# main.net
KiCad netlist of a schematic drawn in Altium Designer
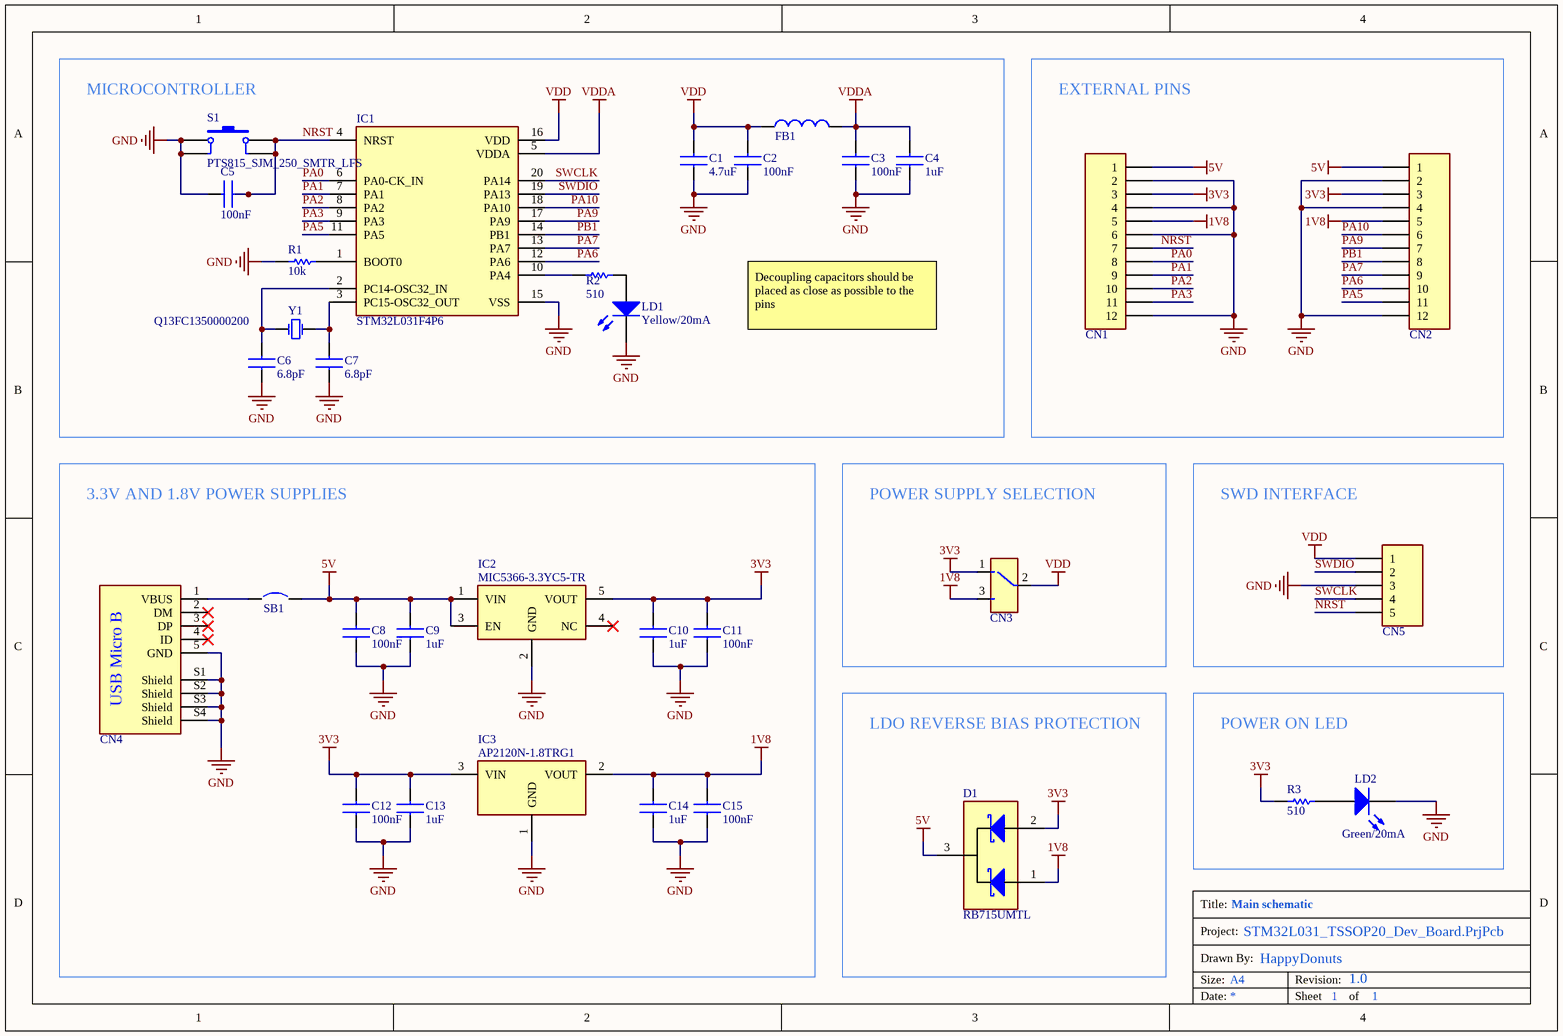
[diagram p0: main.SchDoc]

(export (version "E")
  (design (tool "Eeschema 10.0.6"))
  (components
    (comp (ref "C1")
      (value "4.7uF")
      (footprint "STM32L031_TSSOP20_Dev_Board:CAPC2012X135N")
      (description "Capacitor")
      (fields
        (field (name "MANUFACTURER_PART_NUMBER") "CL21A475KBQNNNE")
        (field (name "MOUSER PART NUMBER") "187-CL21A475KBQNNNE")
      )
      (libsource (lib "STM32L031_TSSOP20_Dev_Board") (part "CL21A475KBQNNNE"))
    )
    (comp (ref "C2")
      (value "100nF")
      (footprint "STM32L031_TSSOP20_Dev_Board:CAPC2012X94N")
      (description "Capacitor")
      (fields
        (field (name "MANUFACTURER_PART_NUMBER") "CL21B104KBCNNNC")
        (field (name "MOUSER PART NUMBER") "187-CL21B104KBCNNNC")
      )
      (libsource (lib "STM32L031_TSSOP20_Dev_Board") (part "CL21B104KBCNNNC"))
    )
    (comp (ref "C3")
      (value "100nF")
      (footprint "STM32L031_TSSOP20_Dev_Board:CAPC2012X94N")
      (description "Capacitor")
      (fields
        (field (name "MANUFACTURER_PART_NUMBER") "CL21B104KBCNNNC")
        (field (name "MOUSER PART NUMBER") "187-CL21B104KBCNNNC")
      )
      (libsource (lib "STM32L031_TSSOP20_Dev_Board") (part "CL21B104KBCNNNC"))
    )
    (comp (ref "C4")
      (value "1uF")
      (footprint "STM32L031_TSSOP20_Dev_Board:CAPC2012X135N")
      (description "Capacitor")
      (fields
        (field (name "MANUFACTURER_PART_NUMBER") "CL21B105KBFNNNE")
        (field (name "MOUSER PART NUMBER") "187-CL21B105KBFNNNE")
      )
      (libsource (lib "STM32L031_TSSOP20_Dev_Board") (part "CL21B105KBFNNNE"))
    )
    (comp (ref "C5")
      (value "100nF")
      (footprint "STM32L031_TSSOP20_Dev_Board:CAPC2012X94N")
      (description "Capacitor")
      (fields
        (field (name "MANUFACTURER_PART_NUMBER") "CL21B104KBCNNNC")
        (field (name "MOUSER PART NUMBER") "187-CL21B104KBCNNNC")
      )
      (libsource (lib "STM32L031_TSSOP20_Dev_Board") (part "CL21B104KBCNNNC"))
    )
    (comp (ref "C6")
      (value "6.8pF")
      (footprint "STM32L031_TSSOP20_Dev_Board:CAPC2012X94N")
      (description "Capacitor")
      (fields
        (field (name "MANUFACTURER_PART_NUMBER") "CC0805CRNPO9BN6R8")
        (field (name "MOUSER PART NUMBER") "603-CC805CRNPO9BN6R8")
      )
      (libsource (lib "STM32L031_TSSOP20_Dev_Board") (part "CC0805CRNPO9BN6R8"))
    )
    (comp (ref "C7")
      (value "6.8pF")
      (footprint "STM32L031_TSSOP20_Dev_Board:CAPC2012X94N")
      (description "Capacitor")
      (fields
        (field (name "MANUFACTURER_PART_NUMBER") "CC0805CRNPO9BN6R8")
        (field (name "MOUSER PART NUMBER") "603-CC805CRNPO9BN6R8")
      )
      (libsource (lib "STM32L031_TSSOP20_Dev_Board") (part "CC0805CRNPO9BN6R8"))
    )
    (comp (ref "C8")
      (value "100nF")
      (footprint "STM32L031_TSSOP20_Dev_Board:CAPC2012X94N")
      (description "Capacitor")
      (fields
        (field (name "MANUFACTURER_PART_NUMBER") "CL21B104KBCNNNC")
        (field (name "MOUSER PART NUMBER") "187-CL21B104KBCNNNC")
      )
      (libsource (lib "STM32L031_TSSOP20_Dev_Board") (part "CL21B104KBCNNNC"))
    )
    (comp (ref "C9")
      (value "1uF")
      (footprint "STM32L031_TSSOP20_Dev_Board:CAPC2012X135N")
      (description "Capacitor")
      (fields
        (field (name "MANUFACTURER_PART_NUMBER") "CL21B105KBFNNNE")
        (field (name "MOUSER PART NUMBER") "187-CL21B105KBFNNNE")
      )
      (libsource (lib "STM32L031_TSSOP20_Dev_Board") (part "CL21B105KBFNNNE"))
    )
    (comp (ref "C10")
      (value "1uF")
      (footprint "STM32L031_TSSOP20_Dev_Board:CAPC2012X135N")
      (description "Capacitor")
      (fields
        (field (name "MANUFACTURER_PART_NUMBER") "CL21B105KBFNNNE")
        (field (name "MOUSER PART NUMBER") "187-CL21B105KBFNNNE")
      )
      (libsource (lib "STM32L031_TSSOP20_Dev_Board") (part "CL21B105KBFNNNE"))
    )
    (comp (ref "C11")
      (value "100nF")
      (footprint "STM32L031_TSSOP20_Dev_Board:CAPC2012X94N")
      (description "Capacitor")
      (fields
        (field (name "MANUFACTURER_PART_NUMBER") "CL21B104KBCNNNC")
        (field (name "MOUSER PART NUMBER") "187-CL21B104KBCNNNC")
      )
      (libsource (lib "STM32L031_TSSOP20_Dev_Board") (part "CL21B104KBCNNNC"))
    )
    (comp (ref "C12")
      (value "100nF")
      (footprint "STM32L031_TSSOP20_Dev_Board:CAPC2012X94N")
      (description "Capacitor")
      (fields
        (field (name "MANUFACTURER_PART_NUMBER") "CL21B104KBCNNNC")
        (field (name "MOUSER PART NUMBER") "187-CL21B104KBCNNNC")
      )
      (libsource (lib "STM32L031_TSSOP20_Dev_Board") (part "CL21B104KBCNNNC"))
    )
    (comp (ref "C13")
      (value "1uF")
      (footprint "STM32L031_TSSOP20_Dev_Board:CAPC2012X135N")
      (description "Capacitor")
      (fields
        (field (name "MANUFACTURER_PART_NUMBER") "CL21B105KBFNNNE")
        (field (name "MOUSER PART NUMBER") "187-CL21B105KBFNNNE")
      )
      (libsource (lib "STM32L031_TSSOP20_Dev_Board") (part "CL21B105KBFNNNE"))
    )
    (comp (ref "C14")
      (value "1uF")
      (footprint "STM32L031_TSSOP20_Dev_Board:CAPC2012X135N")
      (description "Capacitor")
      (fields
        (field (name "MANUFACTURER_PART_NUMBER") "CL21B105KBFNNNE")
        (field (name "MOUSER PART NUMBER") "187-CL21B105KBFNNNE")
      )
      (libsource (lib "STM32L031_TSSOP20_Dev_Board") (part "CL21B105KBFNNNE"))
    )
    (comp (ref "C15")
      (value "100nF")
      (footprint "STM32L031_TSSOP20_Dev_Board:CAPC2012X94N")
      (description "Capacitor")
      (fields
        (field (name "MANUFACTURER_PART_NUMBER") "CL21B104KBCNNNC")
        (field (name "MOUSER PART NUMBER") "187-CL21B104KBCNNNC")
      )
      (libsource (lib "STM32L031_TSSOP20_Dev_Board") (part "CL21B104KBCNNNC"))
    )
    (comp (ref "CN1")
      (value "CN_12PIN")
      (footprint "STM32L031_TSSOP20_Dev_Board:CN_12PIN")
      (description "Connector")
      (libsource (lib "STM32L031_TSSOP20_Dev_Board") (part "CN_12PIN"))
    )
    (comp (ref "CN2")
      (value "CN_12PIN")
      (footprint "STM32L031_TSSOP20_Dev_Board:CN_12PIN")
      (description "Connector")
      (libsource (lib "") (part "CN_12PIN_1"))
    )
    (comp (ref "CN3")
      (value "CN_3PIN")
      (footprint "STM32L031_TSSOP20_Dev_Board:CN_3PIN")
      (description "Connector")
      (libsource (lib "STM32L031_TSSOP20_Dev_Board") (part "CN_3PIN"))
    )
    (comp (ref "CN4")
      (value "USB_B_AE")
      (footprint "STM32L031_TSSOP20_Dev_Board:USB_B_AE")
      (description "USB connector")
      (fields (field (name "ARROW PART NUMBER") "TB67H450FNG,EL"))
      (libsource (lib "STM32L031_TSSOP20_Dev_Board") (part "USB_B_AE"))
    )
    (comp (ref "CN5")
      (value "CN_5PIN")
      (footprint "STM32L031_TSSOP20_Dev_Board:CN_5PIN")
      (description "Connector")
      (libsource (lib "STM32L031_TSSOP20_Dev_Board") (part "CN_5PIN"))
    )
    (comp (ref "D1")
      (value "RB715UMTL")
      (footprint "STM32L031_TSSOP20_Dev_Board:DAN217UMTL")
      (description "Schottky Diode")
      (fields (field (name "MOUSER PART NUMBER") "755-RB715UMTL"))
      (libsource (lib "STM32L031_TSSOP20_Dev_Board") (part "RB715UMTL"))
    )
    (comp (ref "FB1")
      (value "FBMJ2125HS250NT")
      (footprint "STM32L031_TSSOP20_Dev_Board:BEADC2012X105N")
      (description "Ferrite Bead")
      (fields (field (name "MOUSER PART NUMBER") "963-FBMJ2125HS250NT"))
      (libsource (lib "STM32L031_TSSOP20_Dev_Board") (part "FBMJ2125HS250NT"))
    )
    (comp (ref "IC1")
      (value "STM32L031F4P6")
      (footprint "STM32L031_TSSOP20_Dev_Board:SOP65P640X120-20N")
      (description "Integrated Circuit")
      (fields (field (name "MOUSER PART NUMBER") "511-STM32L031F4P6"))
      (libsource (lib "STM32L031_TSSOP20_Dev_Board") (part "STM32L031F4P6"))
    )
    (comp (ref "IC2")
      (value "MIC5366-3.3YC5-TR")
      (footprint "STM32L031_TSSOP20_Dev_Board:SOT65P210X110-5N")
      (description "LDO")
      (fields (field (name "MOUSER PART NUMBER") "998-MIC5366-3.3YC5TR"))
      (libsource (lib "STM32L031_TSSOP20_Dev_Board") (part "MIC5366-3.3YC5-TR"))
    )
    (comp (ref "IC3")
      (value "AP2120N-1.8TRG1")
      (footprint "STM32L031_TSSOP20_Dev_Board:SOT95P230X110-3N")
      (description "LDO")
      (fields (field (name "MOUSER PART NUMBER") "621-AP2120N-1.8TRG1"))
      (libsource (lib "STM32L031_TSSOP20_Dev_Board") (part "AP2120N-1.8TRG1"))
    )
    (comp (ref "LD1")
      (value "Yellow/20mA")
      (footprint "STM32L031_TSSOP20_Dev_Board:LEDC2012X85N_Y")
      (description "LED")
      (fields
        (field (name "MANUFACTURER_PART_NUMBER") "LTST-C171KSKT")
        (field (name "MOUSER PART NUMBER") "859-LTST-C171KSKT")
      )
      (libsource (lib "STM32L031_TSSOP20_Dev_Board") (part "LTST-C171KSKT"))
    )
    (comp (ref "LD2")
      (value "Green/20mA")
      (footprint "STM32L031_TSSOP20_Dev_Board:LEDC2012X85N_G")
      (description "LED")
      (fields
        (field (name "MANUFACTURER_PART_NUMBER") "LTST-C171KGKT")
        (field (name "MOUSER PART NUMBER") "859-LTST-C171KGKT")
      )
      (libsource (lib "STM32L031_TSSOP20_Dev_Board") (part "LTST-C171KGKT"))
    )
    (comp (ref "R1")
      (value "10k")
      (footprint "STM32L031_TSSOP20_Dev_Board:RESC2012X60N")
      (description "Resistor")
      (fields
        (field (name "MANUFACTURER_PART_NUMBER") "RC0805FR-0710KL")
        (field (name "MOUSER PART NUMBER") "603-RC0805FR-0710KL")
      )
      (libsource (lib "STM32L031_TSSOP20_Dev_Board") (part "RC0805FR-0710KL"))
    )
    (comp (ref "R2")
      (value "510")
      (footprint "STM32L031_TSSOP20_Dev_Board:RESC2012X60N")
      (description "Resistor")
      (fields
        (field (name "MANUFACTURER_PART_NUMBER") "RC0805FR-07510RL")
        (field (name "MOUSER PART NUMBER") "603-RC0805FR-07510RL")
      )
      (libsource (lib "STM32L031_TSSOP20_Dev_Board") (part "RC0805FR-07510RL"))
    )
    (comp (ref "R3")
      (value "510")
      (footprint "STM32L031_TSSOP20_Dev_Board:RESC2012X60N")
      (description "Resistor")
      (fields
        (field (name "MANUFACTURER_PART_NUMBER") "RC0805FR-07510RL")
        (field (name "MOUSER PART NUMBER") "603-RC0805FR-07510RL")
      )
      (libsource (lib "STM32L031_TSSOP20_Dev_Board") (part "RC0805FR-07510RL"))
    )
    (comp (ref "S1")
      (value "PTS815_SJM_250_SMTR_LFS")
      (footprint "STM32L031_TSSOP20_Dev_Board:PTS815SJM250SMTRLFS")
      (description "Switch")
      (fields
        (field (name "MANUFACTURER_PART_NUMBER") "PTS815 SJM 250 SMTR LFS")
        (field (name "MOUSER PART NUMBER") "611-PTS815SJM250SMTR")
      )
      (libsource (lib "STM32L031_TSSOP20_Dev_Board") (part "PTS815_SJM_250_SMTR_LFS"))
    )
    (comp (ref "SB1")
      (value "RC0805FR-070RL")
      (footprint "STM32L031_TSSOP20_Dev_Board:RESC2012X60N")
      (description "Jumper (0 ohm)")
      (fields (field (name "MOUSER PART NUMBER") "603-RC0805FR-070RL"))
      (libsource (lib "STM32L031_TSSOP20_Dev_Board") (part "RC0805FR-070RL"))
    )
    (comp (ref "Y1")
      (value "Q13FC1350000200")
      (footprint "STM32L031_TSSOP20_Dev_Board:Q13FC1350000200")
      (description "Crystal")
      (libsource (lib "STM32L031_TSSOP20_Dev_Board") (part "Q13FC1350000200"))
    )
  )
  (nets
    (net (code "1") (name "/NRST") (class "Default")
      (node (ref "C5") (pin "1") (pinfunction "1_1") (pintype "passive"))
      (node (ref "CN1") (pin "7") (pinfunction "7_7") (pintype "passive"))
      (node (ref "CN5") (pin "5") (pinfunction "5_5") (pintype "passive"))
      (node (ref "IC1") (pin "4") (pinfunction "NRST_4") (pintype "passive"))
      (node (ref "S1") (pin "3") (pinfunction "3_3") (pintype "passive"))
      (node (ref "S1") (pin "4") (pinfunction "4_4") (pintype "passive"))
    )
    (net (code "2") (name "/PA0") (class "Default")
      (node (ref "CN1") (pin "8") (pinfunction "8_8") (pintype "passive"))
      (node (ref "IC1") (pin "6") (pinfunction "PA0-CK_IN_6") (pintype "passive"))
    )
    (net (code "3") (name "/PA1") (class "Default")
      (node (ref "CN1") (pin "9") (pinfunction "9_9") (pintype "passive"))
      (node (ref "IC1") (pin "7") (pinfunction "PA1_7") (pintype "passive"))
    )
    (net (code "4") (name "/PA2") (class "Default")
      (node (ref "CN1") (pin "10") (pinfunction "10_10") (pintype "passive"))
      (node (ref "IC1") (pin "8") (pinfunction "PA2_8") (pintype "passive"))
    )
    (net (code "5") (name "/PA3") (class "Default")
      (node (ref "CN1") (pin "11") (pinfunction "11_11") (pintype "passive"))
      (node (ref "IC1") (pin "9") (pinfunction "PA3_9") (pintype "passive"))
    )
    (net (code "6") (name "/PA5") (class "Default")
      (node (ref "CN2") (pin "11") (pinfunction "11_11") (pintype "passive"))
      (node (ref "IC1") (pin "11") (pinfunction "PA5_11") (pintype "passive"))
    )
    (net (code "7") (name "/PA6") (class "Default")
      (node (ref "CN2") (pin "10") (pinfunction "10_10") (pintype "passive"))
      (node (ref "IC1") (pin "12") (pinfunction "PA6_12") (pintype "passive"))
    )
    (net (code "8") (name "/PA7") (class "Default")
      (node (ref "CN2") (pin "9") (pinfunction "9_9") (pintype "passive"))
      (node (ref "IC1") (pin "13") (pinfunction "PA7_13") (pintype "passive"))
    )
    (net (code "9") (name "/PA9") (class "Default")
      (node (ref "CN2") (pin "7") (pinfunction "7_7") (pintype "passive"))
      (node (ref "IC1") (pin "17") (pinfunction "PA9_17") (pintype "passive"))
    )
    (net (code "10") (name "/PA10") (class "Default")
      (node (ref "CN2") (pin "6") (pinfunction "6_6") (pintype "passive"))
      (node (ref "IC1") (pin "18") (pinfunction "PA10_18") (pintype "passive"))
    )
    (net (code "11") (name "/PB1") (class "Default")
      (node (ref "CN2") (pin "8") (pinfunction "8_8") (pintype "passive"))
      (node (ref "IC1") (pin "14") (pinfunction "PB1_14") (pintype "passive"))
    )
    (net (code "12") (name "/SWCLK") (class "Default")
      (node (ref "CN5") (pin "4") (pinfunction "4_4") (pintype "passive"))
      (node (ref "IC1") (pin "20") (pinfunction "PA14_20") (pintype "passive"))
    )
    (net (code "13") (name "/SWDIO") (class "Default")
      (node (ref "CN5") (pin "2") (pinfunction "2_2") (pintype "passive"))
      (node (ref "IC1") (pin "19") (pinfunction "PA13_19") (pintype "passive"))
    )
    (net (code "14") (name "1V8") (class "Default")
      (node (ref "C14") (pin "2") (pinfunction "2_2") (pintype "passive"))
      (node (ref "C15") (pin "2") (pinfunction "2_2") (pintype "passive"))
      (node (ref "CN1") (pin "5") (pinfunction "5_5") (pintype "passive"))
      (node (ref "CN2") (pin "5") (pinfunction "5_5") (pintype "passive"))
      (node (ref "CN3") (pin "3") (pinfunction "3_3") (pintype "passive"))
      (node (ref "D1") (pin "1") (pinfunction "K_1_1") (pintype "passive"))
      (node (ref "IC3") (pin "2") (pinfunction "VOUT_2") (pintype "passive"))
    )
    (net (code "15") (name "3V3") (class "Default")
      (node (ref "C10") (pin "2") (pinfunction "2_2") (pintype "passive"))
      (node (ref "C11") (pin "2") (pinfunction "2_2") (pintype "passive"))
      (node (ref "C12") (pin "2") (pinfunction "2_2") (pintype "passive"))
      (node (ref "C13") (pin "2") (pinfunction "2_2") (pintype "passive"))
      (node (ref "CN1") (pin "3") (pinfunction "3_3") (pintype "passive"))
      (node (ref "CN2") (pin "3") (pinfunction "3_3") (pintype "passive"))
      (node (ref "CN3") (pin "1") (pinfunction "1_1") (pintype "passive"))
      (node (ref "D1") (pin "2") (pinfunction "K_2_2") (pintype "passive"))
      (node (ref "IC2") (pin "5") (pinfunction "VOUT_5") (pintype "passive"))
      (node (ref "IC3") (pin "3") (pinfunction "VIN_3") (pintype "passive"))
      (node (ref "R3") (pin "2") (pinfunction "2_2") (pintype "passive"))
    )
    (net (code "16") (name "5V") (class "Default")
      (node (ref "C8") (pin "2") (pinfunction "2_2") (pintype "passive"))
      (node (ref "C9") (pin "2") (pinfunction "2_2") (pintype "passive"))
      (node (ref "CN1") (pin "1") (pinfunction "1_1") (pintype "passive"))
      (node (ref "CN2") (pin "1") (pinfunction "1_1") (pintype "passive"))
      (node (ref "D1") (pin "3") (pinfunction "COM_A_3") (pintype "passive"))
      (node (ref "IC2") (pin "1") (pinfunction "VIN_1") (pintype "power_in"))
      (node (ref "IC2") (pin "3") (pinfunction "EN_3") (pintype "passive"))
      (node (ref "SB1") (pin "2") (pinfunction "2_2") (pintype "passive"))
    )
    (net (code "17") (name "GND") (class "Default")
      (node (ref "C1") (pin "2") (pinfunction "2_2") (pintype "passive"))
      (node (ref "C10") (pin "1") (pinfunction "1_1") (pintype "passive"))
      (node (ref "C11") (pin "1") (pinfunction "1_1") (pintype "passive"))
      (node (ref "C12") (pin "1") (pinfunction "1_1") (pintype "passive"))
      (node (ref "C13") (pin "1") (pinfunction "1_1") (pintype "passive"))
      (node (ref "C14") (pin "1") (pinfunction "1_1") (pintype "passive"))
      (node (ref "C15") (pin "1") (pinfunction "1_1") (pintype "passive"))
      (node (ref "C2") (pin "1") (pinfunction "1_1") (pintype "passive"))
      (node (ref "C3") (pin "1") (pinfunction "1_1") (pintype "passive"))
      (node (ref "C4") (pin "1") (pinfunction "1_1") (pintype "passive"))
      (node (ref "C5") (pin "2") (pinfunction "2_2") (pintype "passive"))
      (node (ref "C6") (pin "1") (pinfunction "1_1") (pintype "passive"))
      (node (ref "C7") (pin "1") (pinfunction "1_1") (pintype "passive"))
      (node (ref "C8") (pin "1") (pinfunction "1_1") (pintype "passive"))
      (node (ref "C9") (pin "1") (pinfunction "1_1") (pintype "passive"))
      (node (ref "CN1") (pin "12") (pinfunction "12_12") (pintype "passive"))
      (node (ref "CN1") (pin "2") (pinfunction "2_2") (pintype "passive"))
      (node (ref "CN1") (pin "4") (pinfunction "4_4") (pintype "passive"))
      (node (ref "CN1") (pin "6") (pinfunction "6_6") (pintype "passive"))
      (node (ref "CN2") (pin "12") (pinfunction "12_12") (pintype "passive"))
      (node (ref "CN2") (pin "2") (pinfunction "2_2") (pintype "passive"))
      (node (ref "CN2") (pin "4") (pinfunction "4_4") (pintype "passive"))
      (node (ref "CN4") (pin "5") (pinfunction "GND_5") (pintype "passive"))
      (node (ref "CN4") (pin "S1") (pinfunction "Shield_S1") (pintype "passive"))
      (node (ref "CN4") (pin "S2") (pinfunction "Shield_S2") (pintype "passive"))
      (node (ref "CN4") (pin "S3") (pinfunction "Shield_S3") (pintype "passive"))
      (node (ref "CN4") (pin "S4") (pinfunction "Shield_S4") (pintype "passive"))
      (node (ref "CN5") (pin "3") (pinfunction "3_3") (pintype "passive"))
      (node (ref "IC1") (pin "15") (pinfunction "VSS_15") (pintype "passive"))
      (node (ref "IC2") (pin "2") (pinfunction "GND_2") (pintype "power_in"))
      (node (ref "IC3") (pin "1") (pinfunction "GND_1") (pintype "power_in"))
      (node (ref "LD1") (pin "1") (pinfunction "K_1") (pintype "passive"))
      (node (ref "LD2") (pin "1") (pinfunction "K_1") (pintype "passive"))
      (node (ref "R1") (pin "1") (pinfunction "1_1") (pintype "passive"))
      (node (ref "S1") (pin "1") (pinfunction "1_1") (pintype "passive"))
      (node (ref "S1") (pin "2") (pinfunction "2_2") (pintype "passive"))
    )
    (net (code "18") (name "Net-(CN4-VBUS)") (class "Default")
      (node (ref "CN4") (pin "1") (pinfunction "VBUS_1") (pintype "passive"))
      (node (ref "SB1") (pin "1") (pinfunction "1_1") (pintype "passive"))
    )
    (net (code "19") (name "Net-(IC1-BOOT0)") (class "Default")
      (node (ref "IC1") (pin "1") (pinfunction "BOOT0_1") (pintype "passive"))
      (node (ref "R1") (pin "2") (pinfunction "2_2") (pintype "passive"))
    )
    (net (code "20") (name "Net-(IC1-PA4)") (class "Default")
      (node (ref "IC1") (pin "10") (pinfunction "PA4_10") (pintype "passive"))
      (node (ref "R2") (pin "1") (pinfunction "1_1") (pintype "passive"))
    )
    (net (code "21") (name "Net-(IC1-PC14-OSC32_IN)") (class "Default")
      (node (ref "C6") (pin "2") (pinfunction "2_2") (pintype "passive"))
      (node (ref "IC1") (pin "2") (pinfunction "PC14-OSC32_IN_2") (pintype "passive"))
      (node (ref "Y1") (pin "1") (pinfunction "1_1") (pintype "passive"))
    )
    (net (code "22") (name "Net-(IC1-PC15-OSC32_OUT)") (class "Default")
      (node (ref "C7") (pin "2") (pinfunction "2_2") (pintype "passive"))
      (node (ref "IC1") (pin "3") (pinfunction "PC15-OSC32_OUT_3") (pintype "passive"))
      (node (ref "Y1") (pin "2") (pinfunction "2_2") (pintype "passive"))
    )
    (net (code "23") (name "Net-(LD1-A)") (class "Default")
      (node (ref "LD1") (pin "2") (pinfunction "A_2") (pintype "passive"))
      (node (ref "R2") (pin "2") (pinfunction "2_2") (pintype "passive"))
    )
    (net (code "24") (name "Net-(LD2-A)") (class "Default")
      (node (ref "LD2") (pin "2") (pinfunction "A_2") (pintype "passive"))
      (node (ref "R3") (pin "1") (pinfunction "1_1") (pintype "passive"))
    )
    (net (code "25") (name "VDD") (class "Default")
      (node (ref "C1") (pin "1") (pinfunction "1_1") (pintype "passive"))
      (node (ref "C2") (pin "2") (pinfunction "2_2") (pintype "passive"))
      (node (ref "CN3") (pin "2") (pinfunction "2_2") (pintype "passive"))
      (node (ref "CN5") (pin "1") (pinfunction "1_1") (pintype "passive"))
      (node (ref "FB1") (pin "1") (pinfunction "1_1") (pintype "passive"))
      (node (ref "IC1") (pin "16") (pinfunction "VDD_16") (pintype "passive"))
    )
    (net (code "26") (name "VDDA") (class "Default")
      (node (ref "C3") (pin "2") (pinfunction "2_2") (pintype "passive"))
      (node (ref "C4") (pin "2") (pinfunction "2_2") (pintype "passive"))
      (node (ref "FB1") (pin "2") (pinfunction "2_2") (pintype "passive"))
      (node (ref "IC1") (pin "5") (pinfunction "VDDA_5") (pintype "passive"))
    )
    (net (code "27") (name "unconnected-(CN4-DM-Pad2)") (class "Default")
      (node (ref "CN4") (pin "2") (pinfunction "DM_2") (pintype "passive+no_connect"))
    )
    (net (code "28") (name "unconnected-(CN4-DP-Pad3)") (class "Default")
      (node (ref "CN4") (pin "3") (pinfunction "DP_3") (pintype "passive+no_connect"))
    )
    (net (code "29") (name "unconnected-(CN4-ID-Pad4)") (class "Default")
      (node (ref "CN4") (pin "4") (pinfunction "ID_4") (pintype "passive+no_connect"))
    )
    (net (code "30") (name "unconnected-(IC2-NC-Pad4)") (class "Default")
      (node (ref "IC2") (pin "4") (pinfunction "NC_4") (pintype "passive+no_connect"))
    )
  )
)
